# led-ledshaped.net
KiCad netlist of a schematic drawn in EAGLE
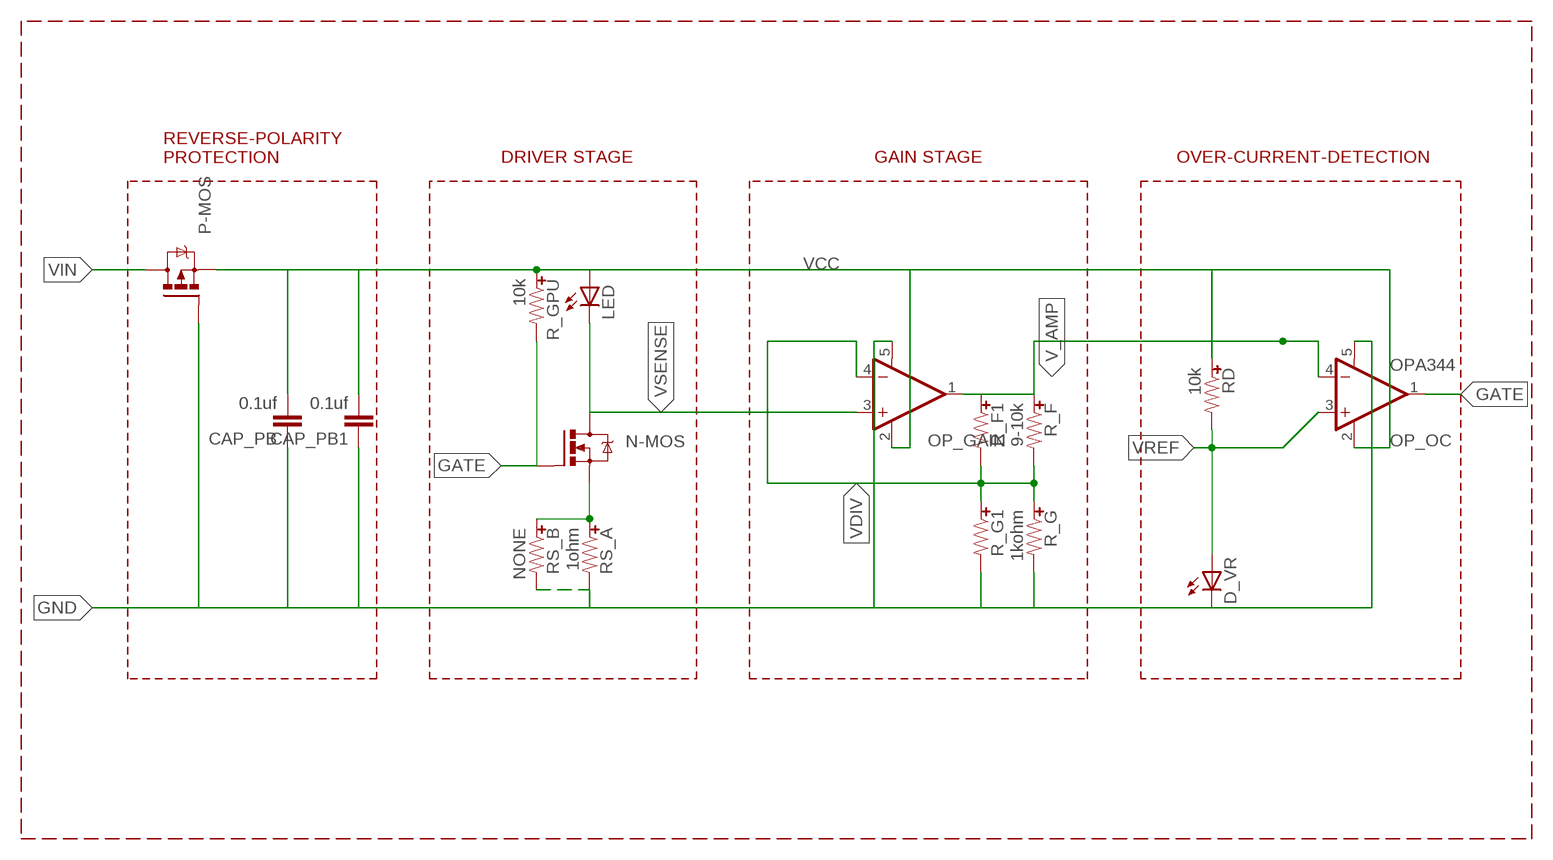
[diagram p0: schematic, sheet 1]

(export (version "E")
  (design (tool "Eeschema 10.0.6"))
  (components
    (comp (ref "CAP_PB")
      (value "0.1uf")
      (footprint "eagle-import:0402-0603-0805-UNIVERSAL")
      (libsource (lib "eagle-import") (part "CAPUNIVERSAL"))
    )
    (comp (ref "CAP_PB1")
      (value "0.1uf")
      (footprint "eagle-import:0402-0603-0805-UNIVERSAL")
      (libsource (lib "eagle-import") (part "CAPUNIVERSAL"))
    )
    (comp (ref "D_VR")
      (value "LEDUNIVERSAL")
      (footprint "eagle-import:0402-0603-0805-UNIVERSAL")
      (libsource (lib "eagle-import") (part "LEDUNIVERSAL"))
    )
    (comp (ref "LED")
      (value "LEDUNIVERSAL")
      (footprint "eagle-import:0402-0603-0805-UNIVERSAL")
      (libsource (lib "eagle-import") (part "LEDUNIVERSAL"))
    )
    (comp (ref "N-MOS")
      (value "MOSFET-NCHANNELSMD")
      (footprint "eagle-import:SOT23-3")
      (libsource (lib "eagle-import") (part "MOSFET-NCHANNELSMD"))
    )
    (comp (ref "OP_GAIN")
      (value "OPA344")
      (footprint "eagle-import:SOT23-5")
      (libsource (lib "eagle-import") (part "OPA344"))
    )
    (comp (ref "OP_OC")
      (value "OPA344")
      (footprint "eagle-import:SOT23-5")
      (libsource (lib "eagle-import") (part "OPA344"))
    )
    (comp (ref "P-MOS")
      (value "MOSFET-PCHANNEL")
      (footprint "eagle-import:SOT23-3")
      (libsource (lib "eagle-import") (part "MOSFET-PCHANNEL"))
    )
    (comp (ref "RD")
      (value "10k")
      (footprint "eagle-import:0402-0603-0805-UNIVERSAL")
      (libsource (lib "eagle-import") (part "RESISTORUNIVERSAL"))
    )
    (comp (ref "RS_A")
      (value "1ohm")
      (footprint "eagle-import:0402-0603-0805-UNIVERSAL")
      (libsource (lib "eagle-import") (part "RESISTORUNIVERSAL"))
    )
    (comp (ref "RS_B")
      (value "NONE")
      (footprint "eagle-import:0402-0603-0805-UNIVERSAL")
      (libsource (lib "eagle-import") (part "RESISTORUNIVERSAL"))
    )
    (comp (ref "R_F")
      (value "9-10k")
      (footprint "eagle-import:0402-0603-0805-UNIVERSAL")
      (libsource (lib "eagle-import") (part "RESISTORUNIVERSAL"))
    )
    (comp (ref "R_F1")
      (value "RESISTORUNIVERSAL")
      (footprint "eagle-import:0402-0603-0805-UNIVERSAL")
      (libsource (lib "eagle-import") (part "RESISTORUNIVERSAL"))
    )
    (comp (ref "R_G")
      (value "1kohm")
      (footprint "eagle-import:0402-0603-0805-UNIVERSAL")
      (libsource (lib "eagle-import") (part "RESISTORUNIVERSAL"))
    )
    (comp (ref "R_G1")
      (value "RESISTORUNIVERSAL")
      (footprint "eagle-import:0402-0603-0805-UNIVERSAL")
      (libsource (lib "eagle-import") (part "RESISTORUNIVERSAL"))
    )
    (comp (ref "R_GPU")
      (value "10k")
      (footprint "eagle-import:0402-0603-0805-UNIVERSAL")
      (libsource (lib "eagle-import") (part "RESISTORUNIVERSAL"))
    )
  )
  (nets
    (net (code "1") (name "/VCC") (class "Default")
      (node (ref "CAP_PB") (pin "+") (pinfunction "2_+") (pintype "passive"))
      (node (ref "CAP_PB1") (pin "+") (pinfunction "2_+") (pintype "passive"))
      (node (ref "LED") (pin "+") (pinfunction "A_+") (pintype "passive"))
      (node (ref "OP_GAIN") (pin "2") (pinfunction "V-_2") (pintype "power_in"))
      (node (ref "OP_OC") (pin "2") (pinfunction "V-_2") (pintype "power_in"))
      (node (ref "P-MOS") (pin "2") (pinfunction "S_2") (pintype "passive"))
      (node (ref "RD") (pin "+") (pinfunction "1_+") (pintype "passive"))
      (node (ref "R_GPU") (pin "+") (pinfunction "1_+") (pintype "passive"))
    )
    (net (code "2") (name "GATE") (class "Default")
      (node (ref "N-MOS") (pin "1") (pinfunction "G_1") (pintype "passive"))
      (node (ref "OP_OC") (pin "1") (pinfunction "OUT_1") (pintype "output"))
      (node (ref "R_GPU") (pin "-") (pinfunction "2_-") (pintype "passive"))
    )
    (net (code "3") (name "GND") (class "Default")
      (node (ref "CAP_PB") (pin "-") (pinfunction "1_-") (pintype "passive"))
      (node (ref "CAP_PB1") (pin "-") (pinfunction "1_-") (pintype "passive"))
      (node (ref "D_VR") (pin "-") (pinfunction "C_-") (pintype "passive"))
      (node (ref "OP_GAIN") (pin "5") (pinfunction "V+_5") (pintype "power_in"))
      (node (ref "OP_OC") (pin "5") (pinfunction "V+_5") (pintype "power_in"))
      (node (ref "P-MOS") (pin "1") (pinfunction "G_1") (pintype "passive"))
      (node (ref "RS_A") (pin "-") (pinfunction "2_-") (pintype "passive"))
      (node (ref "RS_B") (pin "-") (pinfunction "2_-") (pintype "passive"))
      (node (ref "R_G") (pin "-") (pinfunction "2_-") (pintype "passive"))
      (node (ref "R_G1") (pin "-") (pinfunction "2_-") (pintype "passive"))
    )
    (net (code "4") (name "Net-(N-MOS-S)") (class "Default")
      (node (ref "N-MOS") (pin "2") (pinfunction "S_2") (pintype "passive"))
      (node (ref "RS_A") (pin "+") (pinfunction "1_+") (pintype "passive"))
      (node (ref "RS_B") (pin "+") (pinfunction "1_+") (pintype "passive"))
    )
    (net (code "5") (name "VDIV") (class "Default")
      (node (ref "OP_GAIN") (pin "4") (pinfunction "-IN_4") (pintype "input"))
      (node (ref "R_F") (pin "-") (pinfunction "2_-") (pintype "passive"))
      (node (ref "R_F1") (pin "-") (pinfunction "2_-") (pintype "passive"))
      (node (ref "R_G") (pin "+") (pinfunction "1_+") (pintype "passive"))
      (node (ref "R_G1") (pin "+") (pinfunction "1_+") (pintype "passive"))
    )
    (net (code "6") (name "VIN") (class "Default")
      (node (ref "P-MOS") (pin "3") (pinfunction "D_3") (pintype "passive"))
    )
    (net (code "7") (name "VREF") (class "Default")
      (node (ref "D_VR") (pin "+") (pinfunction "A_+") (pintype "passive"))
      (node (ref "OP_OC") (pin "3") (pinfunction "+IN_3") (pintype "input"))
      (node (ref "RD") (pin "-") (pinfunction "2_-") (pintype "passive"))
    )
    (net (code "8") (name "VSENSE") (class "Default")
      (node (ref "LED") (pin "-") (pinfunction "C_-") (pintype "passive"))
      (node (ref "N-MOS") (pin "3") (pinfunction "D_3") (pintype "passive"))
      (node (ref "OP_GAIN") (pin "3") (pinfunction "+IN_3") (pintype "input"))
    )
    (net (code "9") (name "V_AMP") (class "Default")
      (node (ref "OP_GAIN") (pin "1") (pinfunction "OUT_1") (pintype "output"))
      (node (ref "OP_OC") (pin "4") (pinfunction "-IN_4") (pintype "input"))
      (node (ref "R_F") (pin "+") (pinfunction "1_+") (pintype "passive"))
      (node (ref "R_F1") (pin "+") (pinfunction "1_+") (pintype "passive"))
    )
  )
)
